# mm2-ringlight.net
KiCad netlist of a schematic drawn in EAGLE
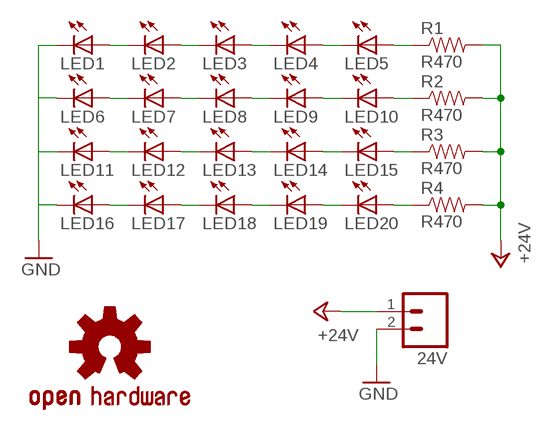
[diagram p0: schematic, sheet 1]

(export (version "E")
  (design (tool "Eeschema 10.0.6"))
  (components
    (comp (ref "24V")
      (value "M02PTH")
      (footprint "eagle-import:1X02")
      (libsource (lib "eagle-import") (part "M02PTH"))
    )
    (comp (ref "LED1")
      (value "LEDCHIPLED_0805")
      (footprint "eagle-import:CHIPLED_0805")
      (libsource (lib "eagle-import") (part "LEDCHIPLED_0805"))
    )
    (comp (ref "LED2")
      (value "LEDCHIPLED_0805")
      (footprint "eagle-import:CHIPLED_0805")
      (libsource (lib "eagle-import") (part "LEDCHIPLED_0805"))
    )
    (comp (ref "LED3")
      (value "LEDCHIPLED_0805")
      (footprint "eagle-import:CHIPLED_0805")
      (libsource (lib "eagle-import") (part "LEDCHIPLED_0805"))
    )
    (comp (ref "LED4")
      (value "LEDCHIPLED_0805")
      (footprint "eagle-import:CHIPLED_0805")
      (libsource (lib "eagle-import") (part "LEDCHIPLED_0805"))
    )
    (comp (ref "LED5")
      (value "LEDCHIPLED_0805")
      (footprint "eagle-import:CHIPLED_0805")
      (libsource (lib "eagle-import") (part "LEDCHIPLED_0805"))
    )
    (comp (ref "LED6")
      (value "LEDCHIPLED_0805")
      (footprint "eagle-import:CHIPLED_0805")
      (libsource (lib "eagle-import") (part "LEDCHIPLED_0805"))
    )
    (comp (ref "LED7")
      (value "LEDCHIPLED_0805")
      (footprint "eagle-import:CHIPLED_0805")
      (libsource (lib "eagle-import") (part "LEDCHIPLED_0805"))
    )
    (comp (ref "LED8")
      (value "LEDCHIPLED_0805")
      (footprint "eagle-import:CHIPLED_0805")
      (libsource (lib "eagle-import") (part "LEDCHIPLED_0805"))
    )
    (comp (ref "LED9")
      (value "LEDCHIPLED_0805")
      (footprint "eagle-import:CHIPLED_0805")
      (libsource (lib "eagle-import") (part "LEDCHIPLED_0805"))
    )
    (comp (ref "LED10")
      (value "LEDCHIPLED_0805")
      (footprint "eagle-import:CHIPLED_0805")
      (libsource (lib "eagle-import") (part "LEDCHIPLED_0805"))
    )
    (comp (ref "LED11")
      (value "LEDCHIPLED_0805")
      (footprint "eagle-import:CHIPLED_0805")
      (libsource (lib "eagle-import") (part "LEDCHIPLED_0805"))
    )
    (comp (ref "LED12")
      (value "LEDCHIPLED_0805")
      (footprint "eagle-import:CHIPLED_0805")
      (libsource (lib "eagle-import") (part "LEDCHIPLED_0805"))
    )
    (comp (ref "LED13")
      (value "LEDCHIPLED_0805")
      (footprint "eagle-import:CHIPLED_0805")
      (libsource (lib "eagle-import") (part "LEDCHIPLED_0805"))
    )
    (comp (ref "LED14")
      (value "LEDCHIPLED_0805")
      (footprint "eagle-import:CHIPLED_0805")
      (libsource (lib "eagle-import") (part "LEDCHIPLED_0805"))
    )
    (comp (ref "LED15")
      (value "LEDCHIPLED_0805")
      (footprint "eagle-import:CHIPLED_0805")
      (libsource (lib "eagle-import") (part "LEDCHIPLED_0805"))
    )
    (comp (ref "LED16")
      (value "LEDCHIPLED_0805")
      (footprint "eagle-import:CHIPLED_0805")
      (libsource (lib "eagle-import") (part "LEDCHIPLED_0805"))
    )
    (comp (ref "LED17")
      (value "LEDCHIPLED_0805")
      (footprint "eagle-import:CHIPLED_0805")
      (libsource (lib "eagle-import") (part "LEDCHIPLED_0805"))
    )
    (comp (ref "LED18")
      (value "LEDCHIPLED_0805")
      (footprint "eagle-import:CHIPLED_0805")
      (libsource (lib "eagle-import") (part "LEDCHIPLED_0805"))
    )
    (comp (ref "LED19")
      (value "LEDCHIPLED_0805")
      (footprint "eagle-import:CHIPLED_0805")
      (libsource (lib "eagle-import") (part "LEDCHIPLED_0805"))
    )
    (comp (ref "LED20")
      (value "LEDCHIPLED_0805")
      (footprint "eagle-import:CHIPLED_0805")
      (libsource (lib "eagle-import") (part "LEDCHIPLED_0805"))
    )
    (comp (ref "R1")
      (value "R470")
      (footprint "eagle-import:0805")
      (libsource (lib "eagle-import") (part "RESISTOR0805-RES"))
    )
    (comp (ref "R2")
      (value "R470")
      (footprint "eagle-import:0805")
      (libsource (lib "eagle-import") (part "RESISTOR0805-RES"))
    )
    (comp (ref "R3")
      (value "R470")
      (footprint "eagle-import:0805")
      (libsource (lib "eagle-import") (part "RESISTOR0805-RES"))
    )
    (comp (ref "R4")
      (value "R470")
      (footprint "eagle-import:0805")
      (libsource (lib "eagle-import") (part "RESISTOR0805-RES"))
    )
    (comp (ref "U$1")
      (value "OSHW-LOGOS")
      (footprint "eagle-import:OSHW-LOGO-S")
      (libsource (lib "eagle-import") (part "OSHW-LOGOS"))
    )
  )
  (nets
    (net (code "1") (name "+24V") (class "Default")
      (node (ref "24V") (pin "1") (pinfunction "1_1") (pintype "passive"))
      (node (ref "R1") (pin "2") (pinfunction "2_2") (pintype "passive"))
      (node (ref "R2") (pin "2") (pinfunction "2_2") (pintype "passive"))
      (node (ref "R3") (pin "2") (pinfunction "2_2") (pintype "passive"))
      (node (ref "R4") (pin "2") (pinfunction "2_2") (pintype "passive"))
    )
    (net (code "2") (name "GND") (class "Default")
      (node (ref "24V") (pin "2") (pinfunction "2_2") (pintype "passive"))
      (node (ref "LED1") (pin "C") (pinfunction "C_C") (pintype "passive"))
      (node (ref "LED11") (pin "C") (pinfunction "C_C") (pintype "passive"))
      (node (ref "LED16") (pin "C") (pinfunction "C_C") (pintype "passive"))
      (node (ref "LED6") (pin "C") (pinfunction "C_C") (pintype "passive"))
    )
    (net (code "3") (name "Net-(LED1-PadA)") (class "Default")
      (node (ref "LED1") (pin "A") (pinfunction "A_A") (pintype "passive"))
      (node (ref "LED2") (pin "C") (pinfunction "C_C") (pintype "passive"))
    )
    (net (code "4") (name "Net-(LED2-PadA)") (class "Default")
      (node (ref "LED2") (pin "A") (pinfunction "A_A") (pintype "passive"))
      (node (ref "LED3") (pin "C") (pinfunction "C_C") (pintype "passive"))
    )
    (net (code "5") (name "Net-(LED3-PadA)") (class "Default")
      (node (ref "LED3") (pin "A") (pinfunction "A_A") (pintype "passive"))
      (node (ref "LED4") (pin "C") (pinfunction "C_C") (pintype "passive"))
    )
    (net (code "6") (name "Net-(LED4-PadA)") (class "Default")
      (node (ref "LED4") (pin "A") (pinfunction "A_A") (pintype "passive"))
      (node (ref "LED5") (pin "C") (pinfunction "C_C") (pintype "passive"))
    )
    (net (code "7") (name "Net-(LED5-PadA)") (class "Default")
      (node (ref "LED5") (pin "A") (pinfunction "A_A") (pintype "passive"))
      (node (ref "R1") (pin "1") (pinfunction "1_1") (pintype "passive"))
    )
    (net (code "8") (name "Net-(LED6-PadA)") (class "Default")
      (node (ref "LED6") (pin "A") (pinfunction "A_A") (pintype "passive"))
      (node (ref "LED7") (pin "C") (pinfunction "C_C") (pintype "passive"))
    )
    (net (code "9") (name "Net-(LED7-PadA)") (class "Default")
      (node (ref "LED7") (pin "A") (pinfunction "A_A") (pintype "passive"))
      (node (ref "LED8") (pin "C") (pinfunction "C_C") (pintype "passive"))
    )
    (net (code "10") (name "Net-(LED8-PadA)") (class "Default")
      (node (ref "LED8") (pin "A") (pinfunction "A_A") (pintype "passive"))
      (node (ref "LED9") (pin "C") (pinfunction "C_C") (pintype "passive"))
    )
    (net (code "11") (name "Net-(LED10-PadA)") (class "Default")
      (node (ref "LED10") (pin "A") (pinfunction "A_A") (pintype "passive"))
      (node (ref "R2") (pin "1") (pinfunction "1_1") (pintype "passive"))
    )
    (net (code "12") (name "Net-(LED10-PadC)") (class "Default")
      (node (ref "LED10") (pin "C") (pinfunction "C_C") (pintype "passive"))
      (node (ref "LED9") (pin "A") (pinfunction "A_A") (pintype "passive"))
    )
    (net (code "13") (name "Net-(LED11-PadA)") (class "Default")
      (node (ref "LED11") (pin "A") (pinfunction "A_A") (pintype "passive"))
      (node (ref "LED12") (pin "C") (pinfunction "C_C") (pintype "passive"))
    )
    (net (code "14") (name "Net-(LED12-PadA)") (class "Default")
      (node (ref "LED12") (pin "A") (pinfunction "A_A") (pintype "passive"))
      (node (ref "LED13") (pin "C") (pinfunction "C_C") (pintype "passive"))
    )
    (net (code "15") (name "Net-(LED13-PadA)") (class "Default")
      (node (ref "LED13") (pin "A") (pinfunction "A_A") (pintype "passive"))
      (node (ref "LED14") (pin "C") (pinfunction "C_C") (pintype "passive"))
    )
    (net (code "16") (name "Net-(LED14-PadA)") (class "Default")
      (node (ref "LED14") (pin "A") (pinfunction "A_A") (pintype "passive"))
      (node (ref "LED15") (pin "C") (pinfunction "C_C") (pintype "passive"))
    )
    (net (code "17") (name "Net-(LED15-PadA)") (class "Default")
      (node (ref "LED15") (pin "A") (pinfunction "A_A") (pintype "passive"))
      (node (ref "R3") (pin "1") (pinfunction "1_1") (pintype "passive"))
    )
    (net (code "18") (name "Net-(LED16-PadA)") (class "Default")
      (node (ref "LED16") (pin "A") (pinfunction "A_A") (pintype "passive"))
      (node (ref "LED17") (pin "C") (pinfunction "C_C") (pintype "passive"))
    )
    (net (code "19") (name "Net-(LED17-PadA)") (class "Default")
      (node (ref "LED17") (pin "A") (pinfunction "A_A") (pintype "passive"))
      (node (ref "LED18") (pin "C") (pinfunction "C_C") (pintype "passive"))
    )
    (net (code "20") (name "Net-(LED18-PadA)") (class "Default")
      (node (ref "LED18") (pin "A") (pinfunction "A_A") (pintype "passive"))
      (node (ref "LED19") (pin "C") (pinfunction "C_C") (pintype "passive"))
    )
    (net (code "21") (name "Net-(LED19-PadA)") (class "Default")
      (node (ref "LED19") (pin "A") (pinfunction "A_A") (pintype "passive"))
      (node (ref "LED20") (pin "C") (pinfunction "C_C") (pintype "passive"))
    )
    (net (code "22") (name "Net-(LED20-PadA)") (class "Default")
      (node (ref "LED20") (pin "A") (pinfunction "A_A") (pintype "passive"))
      (node (ref "R4") (pin "1") (pinfunction "1_1") (pintype "passive"))
    )
  )
)
